# RigidPCBSensor_2withground17.net
KiCad netlist of a schematic drawn in EAGLE
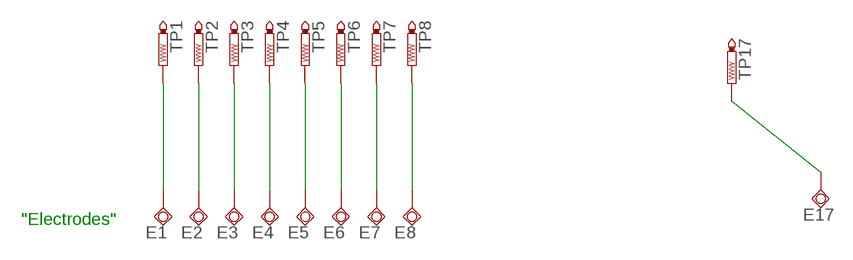
[diagram p0: schematic, sheet 1]

(export (version "E")
  (design (tool "Eeschema 10.0.6"))
  (components
    (comp (ref "E1")
      (value "TPSQTP15R")
      (footprint "eagle-import:TP15R")
      (libsource (lib "eagle-import") (part "TPSQTP15R"))
    )
    (comp (ref "E2")
      (value "TPSQTP15R")
      (footprint "eagle-import:TP15R")
      (libsource (lib "eagle-import") (part "TPSQTP15R"))
    )
    (comp (ref "E3")
      (value "TPSQTP15R")
      (footprint "eagle-import:TP15R")
      (libsource (lib "eagle-import") (part "TPSQTP15R"))
    )
    (comp (ref "E4")
      (value "TPSQTP15R")
      (footprint "eagle-import:TP15R")
      (libsource (lib "eagle-import") (part "TPSQTP15R"))
    )
    (comp (ref "E5")
      (value "TPSQTP15R")
      (footprint "eagle-import:TP15R")
      (libsource (lib "eagle-import") (part "TPSQTP15R"))
    )
    (comp (ref "E6")
      (value "TPSQTP15R")
      (footprint "eagle-import:TP15R")
      (libsource (lib "eagle-import") (part "TPSQTP15R"))
    )
    (comp (ref "E7")
      (value "TPSQTP15R")
      (footprint "eagle-import:TP15R")
      (libsource (lib "eagle-import") (part "TPSQTP15R"))
    )
    (comp (ref "E8")
      (value "TPSQTP15R")
      (footprint "eagle-import:TP15R")
      (libsource (lib "eagle-import") (part "TPSQTP15R"))
    )
    (comp (ref "E17")
      (value "TPSQTP15R")
      (footprint "eagle-import:TP15R")
      (libsource (lib "eagle-import") (part "TPSQTP15R"))
    )
    (comp (ref "TP1")
      (value "PTR1")
      (footprint "eagle-import:TP10SQLONG")
      (libsource (lib "eagle-import") (part "PTR1"))
    )
    (comp (ref "TP2")
      (value "PTR1")
      (footprint "eagle-import:TP10SQLONG")
      (libsource (lib "eagle-import") (part "PTR1"))
    )
    (comp (ref "TP3")
      (value "PTR1")
      (footprint "eagle-import:TP10SQLONG")
      (libsource (lib "eagle-import") (part "PTR1"))
    )
    (comp (ref "TP4")
      (value "PTR1")
      (footprint "eagle-import:TP10SQLONG")
      (libsource (lib "eagle-import") (part "PTR1"))
    )
    (comp (ref "TP5")
      (value "PTR1")
      (footprint "eagle-import:TP10SQLONG")
      (libsource (lib "eagle-import") (part "PTR1"))
    )
    (comp (ref "TP6")
      (value "PTR1")
      (footprint "eagle-import:TP10SQLONG")
      (libsource (lib "eagle-import") (part "PTR1"))
    )
    (comp (ref "TP7")
      (value "PTR1")
      (footprint "eagle-import:TP10SQLONG")
      (libsource (lib "eagle-import") (part "PTR1"))
    )
    (comp (ref "TP8")
      (value "PTR1")
      (footprint "eagle-import:TP10SQLONG")
      (libsource (lib "eagle-import") (part "PTR1"))
    )
    (comp (ref "TP17")
      (value "PTR1")
      (footprint "eagle-import:TP10SQLONG")
      (libsource (lib "eagle-import") (part "PTR1"))
    )
  )
  (nets
    (net (code "1") (name "Net-(E1-PadTP)") (class "Default")
      (node (ref "E1") (pin "TP") (pinfunction "TP_TP") (pintype "input"))
      (node (ref "TP1") (pin "TP") (pinfunction "TP_TP") (pintype "input"))
    )
    (net (code "2") (name "Net-(E2-PadTP)") (class "Default")
      (node (ref "E2") (pin "TP") (pinfunction "TP_TP") (pintype "input"))
      (node (ref "TP2") (pin "TP") (pinfunction "TP_TP") (pintype "input"))
    )
    (net (code "3") (name "Net-(E3-PadTP)") (class "Default")
      (node (ref "E3") (pin "TP") (pinfunction "TP_TP") (pintype "input"))
      (node (ref "TP3") (pin "TP") (pinfunction "TP_TP") (pintype "input"))
    )
    (net (code "4") (name "Net-(E4-PadTP)") (class "Default")
      (node (ref "E4") (pin "TP") (pinfunction "TP_TP") (pintype "input"))
      (node (ref "TP4") (pin "TP") (pinfunction "TP_TP") (pintype "input"))
    )
    (net (code "5") (name "Net-(E5-PadTP)") (class "Default")
      (node (ref "E5") (pin "TP") (pinfunction "TP_TP") (pintype "input"))
      (node (ref "TP5") (pin "TP") (pinfunction "TP_TP") (pintype "input"))
    )
    (net (code "6") (name "Net-(E6-PadTP)") (class "Default")
      (node (ref "E6") (pin "TP") (pinfunction "TP_TP") (pintype "input"))
      (node (ref "TP6") (pin "TP") (pinfunction "TP_TP") (pintype "input"))
    )
    (net (code "7") (name "Net-(E7-PadTP)") (class "Default")
      (node (ref "E7") (pin "TP") (pinfunction "TP_TP") (pintype "input"))
      (node (ref "TP7") (pin "TP") (pinfunction "TP_TP") (pintype "input"))
    )
    (net (code "8") (name "Net-(E8-PadTP)") (class "Default")
      (node (ref "E8") (pin "TP") (pinfunction "TP_TP") (pintype "input"))
      (node (ref "TP8") (pin "TP") (pinfunction "TP_TP") (pintype "input"))
    )
    (net (code "9") (name "Net-(E17-PadTP)") (class "Default")
      (node (ref "E17") (pin "TP") (pinfunction "TP_TP") (pintype "input"))
      (node (ref "TP17") (pin "TP") (pinfunction "TP_TP") (pintype "input"))
    )
  )
)
